# funky_super_usb_r2.net
KiCad netlist of a schematic drawn in EAGLE
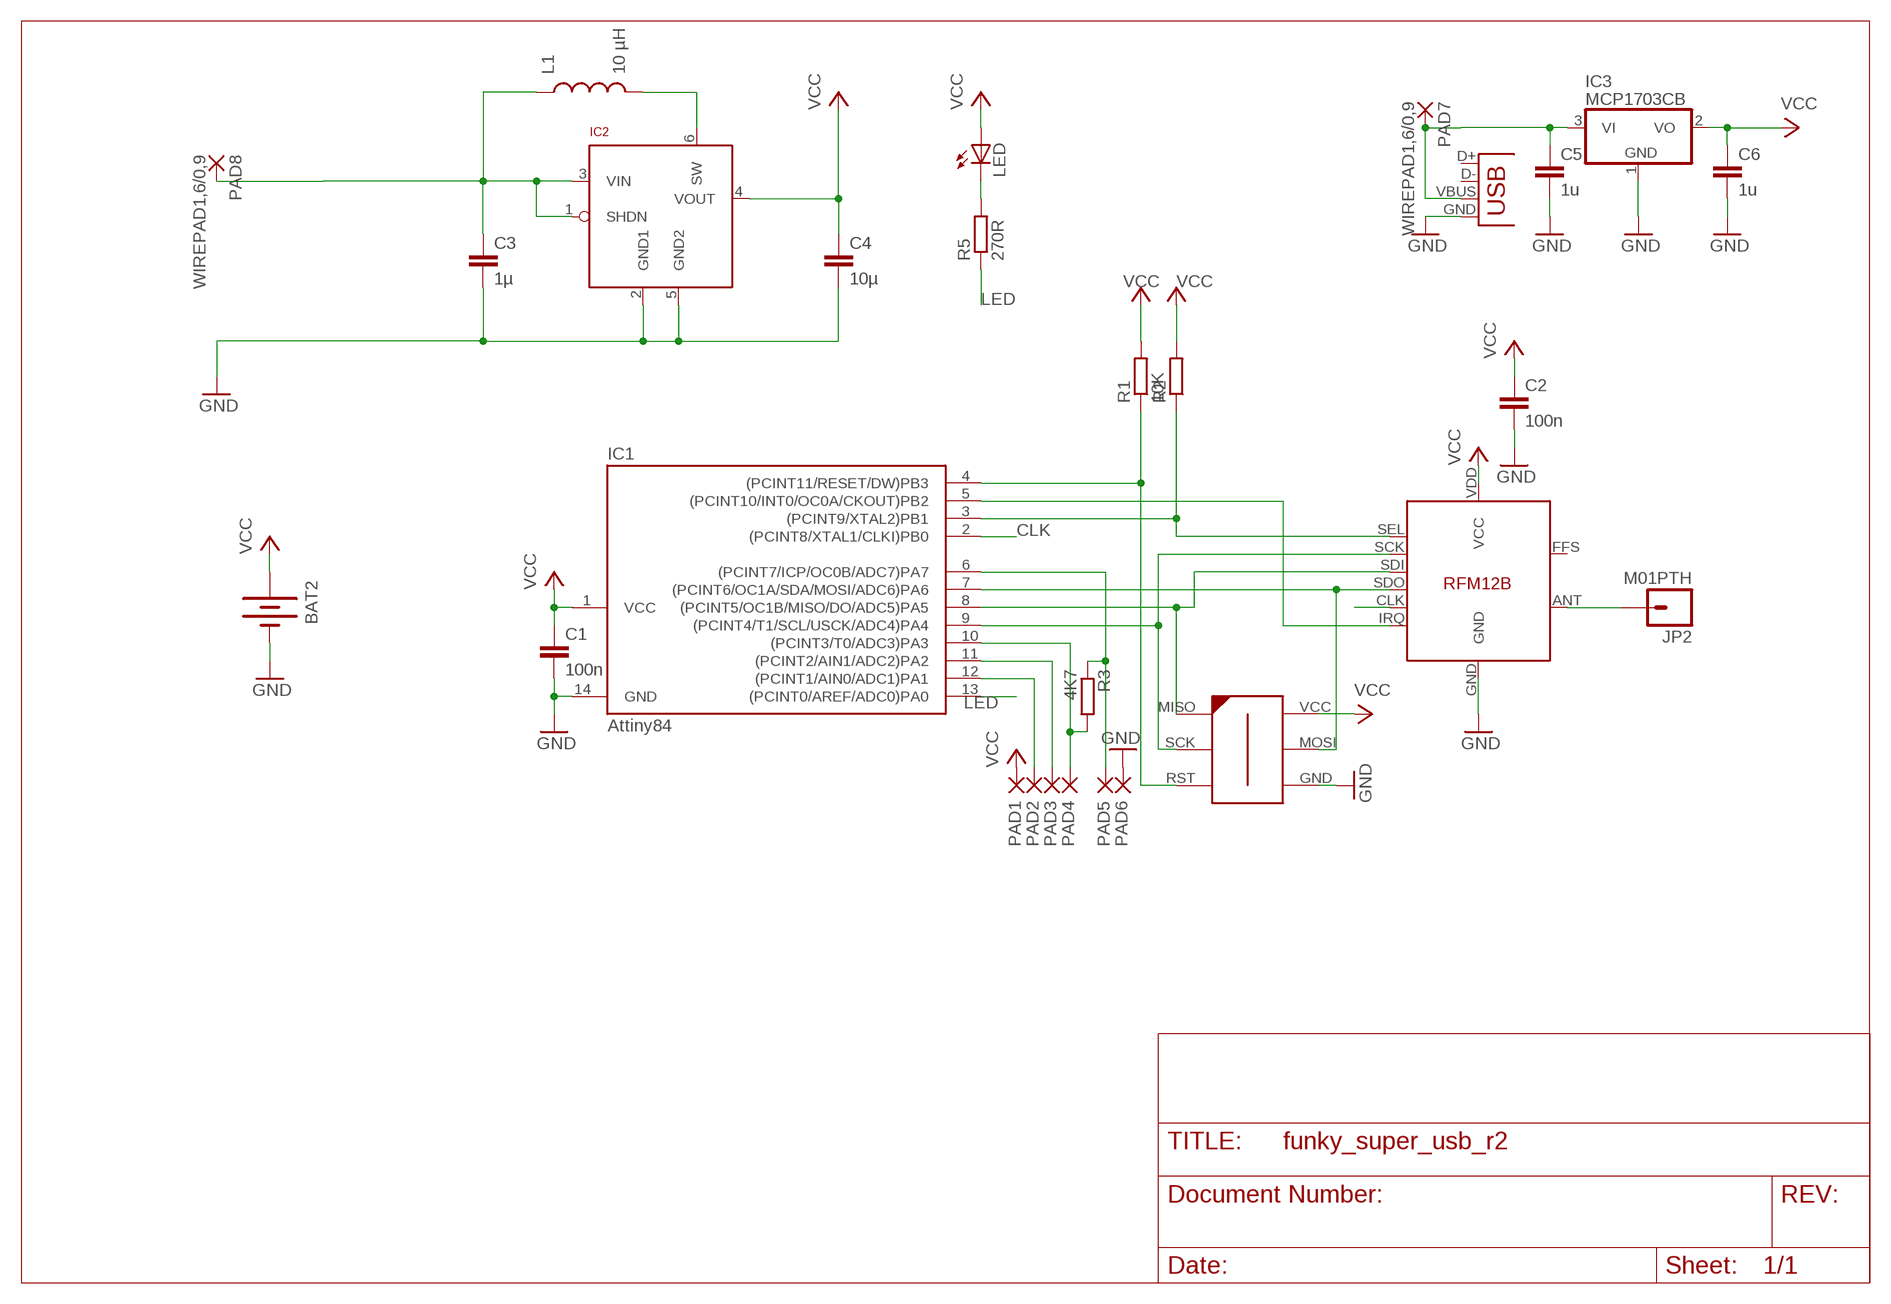
[diagram p0: schematic, sheet 1]

(export (version "E")
  (design (tool "Eeschema 10.0.6"))
  (components
    (comp (ref "BAT2")
      (value "BATTERY20PTH")
      (footprint "eagle-import:BATTCOM_20MM_PTH")
      (libsource (lib "eagle-import") (part "BATTERY20PTH"))
    )
    (comp (ref "C1")
      (value "100n")
      (footprint "eagle-import:C0603K")
      (libsource (lib "eagle-import") (part "C-EUC0603K"))
    )
    (comp (ref "C2")
      (value "100n")
      (footprint "eagle-import:C0603K")
      (libsource (lib "eagle-import") (part "C-EUC0603K"))
    )
    (comp (ref "C3")
      (value "1µ")
      (footprint "eagle-import:0603-CAP")
      (libsource (lib "eagle-import") (part "CAP0603-CAP"))
    )
    (comp (ref "C4")
      (value "10µ")
      (footprint "eagle-import:0805")
      (libsource (lib "eagle-import") (part "CAP0805"))
    )
    (comp (ref "C5")
      (value "1u")
      (footprint "eagle-import:C0603K")
      (libsource (lib "eagle-import") (part "C-EUC0603K"))
    )
    (comp (ref "C6")
      (value "1u")
      (footprint "eagle-import:C0603K")
      (libsource (lib "eagle-import") (part "C-EUC0603K"))
    )
    (comp (ref "IC1")
      (value "Attiny84")
      (footprint "eagle-import:SOIC14")
      (libsource (lib "eagle-import") (part "TINY24/44/84-SSU"))
    )
    (comp (ref "IC2")
      (value "LTC3525")
      (footprint "eagle-import:SC70")
      (libsource (lib "eagle-import") (part "LTC3525"))
    )
    (comp (ref "IC3")
      (value "MCP1703CB")
      (footprint "eagle-import:SOT23")
      (libsource (lib "eagle-import") (part "MCP1703CB"))
    )
    (comp (ref "JP2")
      (value "M01PTH")
      (footprint "eagle-import:1X01")
      (libsource (lib "eagle-import") (part "M01PTH"))
    )
    (comp (ref "L1")
      (value "10 µH")
      (footprint "eagle-import:1210")
      (libsource (lib "eagle-import") (part "INDUCTOR1210"))
    )
    (comp (ref "LED")
      (value "LED0603")
      (footprint "eagle-import:LED-0603")
      (libsource (lib "eagle-import") (part "LED0603"))
    )
    (comp (ref "PAD1")
      (value "SMD2")
      (footprint "eagle-import:SMD1,27-2,54")
      (libsource (lib "eagle-import") (part "SMD2"))
    )
    (comp (ref "PAD2")
      (value "SMD2")
      (footprint "eagle-import:SMD1,27-2,54")
      (libsource (lib "eagle-import") (part "SMD2"))
    )
    (comp (ref "PAD3")
      (value "SMD2")
      (footprint "eagle-import:SMD1,27-2,54")
      (libsource (lib "eagle-import") (part "SMD2"))
    )
    (comp (ref "PAD4")
      (value "SMD2")
      (footprint "eagle-import:SMD1,27-2,54")
      (libsource (lib "eagle-import") (part "SMD2"))
    )
    (comp (ref "PAD5")
      (value "SMD2")
      (footprint "eagle-import:SMD1,27-2,54")
      (libsource (lib "eagle-import") (part "SMD2"))
    )
    (comp (ref "PAD6")
      (value "SMD2")
      (footprint "eagle-import:SMD1,27-2,54")
      (libsource (lib "eagle-import") (part "SMD2"))
    )
    (comp (ref "PAD7")
      (value "WIREPAD1,6/0,9")
      (footprint "eagle-import:1,6_0,9")
      (libsource (lib "eagle-import") (part "WIREPAD1,6/0,9"))
    )
    (comp (ref "PAD8")
      (value "WIREPAD1,6/0,9")
      (footprint "eagle-import:1,6_0,9")
      (libsource (lib "eagle-import") (part "WIREPAD1,6/0,9"))
    )
    (comp (ref "R1")
      (value "10K")
      (footprint "eagle-import:R0603")
      (libsource (lib "eagle-import") (part "R-EU_R0603"))
    )
    (comp (ref "R2")
      (value "R-EU_R0603")
      (footprint "eagle-import:R0603")
      (libsource (lib "eagle-import") (part "R-EU_R0603"))
    )
    (comp (ref "R3")
      (value "4K7")
      (footprint "eagle-import:R0603")
      (libsource (lib "eagle-import") (part "R-EU_R0603"))
    )
    (comp (ref "R5")
      (value "270R")
      (footprint "eagle-import:R0603")
      (libsource (lib "eagle-import") (part "R-EU_R0603"))
    )
    (comp (ref "RFM12B")
      (value "RFM12B")
      (footprint "eagle-import:RFM12B")
      (libsource (lib "eagle-import") (part "RFM12B"))
    )
    (comp (ref "U$2")
      (value "AVR-ISP-6-EDGE")
      (footprint "eagle-import:6PAD_ISP")
      (libsource (lib "eagle-import") (part "AVR-ISP-6-EDGE"))
    )
    (comp (ref "X1")
      (value "USB-MICROB")
      (footprint "eagle-import:USB-MICROB")
      (libsource (lib "eagle-import") (part "USB-MICROB"))
    )
  )
  (nets
    (net (code "1") (name "/CLK") (class "Default")
      (node (ref "IC1") (pin "2") (pinfunction "(PCINT8/XTAL1/CLKI)PB0_2") (pintype "bidirectional"))
      (node (ref "RFM12B") (pin "CLK") (pinfunction "CLK_CLK") (pintype "output"))
    )
    (net (code "2") (name "/LED") (class "Default")
      (node (ref "IC1") (pin "13") (pinfunction "(PCINT0/AREF/ADC0)PA0_13") (pintype "bidirectional"))
      (node (ref "R5") (pin "1") (pinfunction "1_1") (pintype "passive"))
    )
    (net (code "3") (name "GND") (class "Default")
      (node (ref "BAT2") (pin "2") (pinfunction "-_2") (pintype "power_in"))
      (node (ref "C1") (pin "2") (pinfunction "2_2") (pintype "passive"))
      (node (ref "C2") (pin "2") (pinfunction "2_2") (pintype "passive"))
      (node (ref "C3") (pin "2") (pinfunction "2_2") (pintype "passive"))
      (node (ref "C4") (pin "2") (pinfunction "2_2") (pintype "passive"))
      (node (ref "C5") (pin "2") (pinfunction "2_2") (pintype "passive"))
      (node (ref "C6") (pin "2") (pinfunction "2_2") (pintype "passive"))
      (node (ref "IC1") (pin "14") (pinfunction "GND_14") (pintype "power_in"))
      (node (ref "IC2") (pin "2") (pinfunction "GND1_2") (pintype "power_in"))
      (node (ref "IC2") (pin "5") (pinfunction "GND2_5") (pintype "power_in"))
      (node (ref "IC3") (pin "1") (pinfunction "GND_1") (pintype "passive"))
      (node (ref "PAD6") (pin "1") (pinfunction "P_1") (pintype "passive"))
      (node (ref "RFM12B") (pin "GND") (pinfunction "GND_GND") (pintype "power_in"))
      (node (ref "U$2") (pin "GND") (pinfunction "P$4_GND") (pintype "bidirectional"))
      (node (ref "X1") (pin "GND") (pinfunction "GND_GND") (pintype "bidirectional"))
    )
    (net (code "4") (name "Net-(IC1-(PCINT1{slash}AIN0{slash}ADC1)PA1)") (class "Default")
      (node (ref "IC1") (pin "12") (pinfunction "(PCINT1/AIN0/ADC1)PA1_12") (pintype "bidirectional"))
      (node (ref "PAD2") (pin "1") (pinfunction "P_1") (pintype "passive"))
    )
    (net (code "5") (name "Net-(IC1-(PCINT2{slash}AIN1{slash}ADC2)PA2)") (class "Default")
      (node (ref "IC1") (pin "11") (pinfunction "(PCINT2/AIN1/ADC2)PA2_11") (pintype "bidirectional"))
      (node (ref "PAD3") (pin "1") (pinfunction "P_1") (pintype "passive"))
    )
    (net (code "6") (name "Net-(IC1-(PCINT3{slash}T0{slash}ADC3)PA3)") (class "Default")
      (node (ref "IC1") (pin "10") (pinfunction "(PCINT3/T0/ADC3)PA3_10") (pintype "bidirectional"))
      (node (ref "PAD4") (pin "1") (pinfunction "P_1") (pintype "passive"))
      (node (ref "R3") (pin "2") (pinfunction "2_2") (pintype "passive"))
    )
    (net (code "7") (name "Net-(IC1-(PCINT4{slash}T1{slash}SCL{slash}USCK{slash}ADC4)PA4)") (class "Default")
      (node (ref "IC1") (pin "9") (pinfunction "(PCINT4/T1/SCL/USCK/ADC4)PA4_9") (pintype "bidirectional"))
      (node (ref "RFM12B") (pin "SCK") (pinfunction "SCK_SCK") (pintype "input"))
      (node (ref "U$2") (pin "SCK") (pinfunction "P$2_SCK") (pintype "bidirectional"))
    )
    (net (code "8") (name "Net-(IC1-(PCINT5{slash}OC1B{slash}MISO{slash}DO{slash}ADC5)PA5)") (class "Default")
      (node (ref "IC1") (pin "8") (pinfunction "(PCINT5/OC1B/MISO/DO/ADC5)PA5_8") (pintype "bidirectional"))
      (node (ref "RFM12B") (pin "SDI") (pinfunction "SDI_SDI") (pintype "input"))
      (node (ref "U$2") (pin "MISO") (pinfunction "P$1_MISO") (pintype "bidirectional"))
    )
    (net (code "9") (name "Net-(IC1-(PCINT6{slash}OC1A{slash}SDA{slash}MOSI{slash}ADC6)PA6)") (class "Default")
      (node (ref "IC1") (pin "7") (pinfunction "(PCINT6/OC1A/SDA/MOSI/ADC6)PA6_7") (pintype "bidirectional"))
      (node (ref "RFM12B") (pin "SDO") (pinfunction "SDO_SDO") (pintype "output"))
      (node (ref "U$2") (pin "MOSI") (pinfunction "P$5_MOSI") (pintype "bidirectional"))
    )
    (net (code "10") (name "Net-(IC1-(PCINT7{slash}ICP{slash}OC0B{slash}ADC7)PA7)") (class "Default")
      (node (ref "IC1") (pin "6") (pinfunction "(PCINT7/ICP/OC0B/ADC7)PA7_6") (pintype "bidirectional"))
      (node (ref "PAD5") (pin "1") (pinfunction "P_1") (pintype "passive"))
      (node (ref "R3") (pin "1") (pinfunction "1_1") (pintype "passive"))
    )
    (net (code "11") (name "Net-(IC1-(PCINT9{slash}XTAL2)PB1)") (class "Default")
      (node (ref "IC1") (pin "3") (pinfunction "(PCINT9/XTAL2)PB1_3") (pintype "bidirectional"))
      (node (ref "R2") (pin "1") (pinfunction "1_1") (pintype "passive"))
      (node (ref "RFM12B") (pin "SEL") (pinfunction "SEL_SEL") (pintype "input"))
    )
    (net (code "12") (name "Net-(IC1-(PCINT10{slash}INT0{slash}OC0A{slash}CKOUT)PB2)") (class "Default")
      (node (ref "IC1") (pin "5") (pinfunction "(PCINT10/INT0/OC0A/CKOUT)PB2_5") (pintype "bidirectional"))
      (node (ref "RFM12B") (pin "IRQ") (pinfunction "IRQ_IRQ") (pintype "open_collector"))
    )
    (net (code "13") (name "Net-(IC1-(PCINT11{slash}RESET{slash}DW)PB3)") (class "Default")
      (node (ref "IC1") (pin "4") (pinfunction "(PCINT11/RESET/DW)PB3_4") (pintype "bidirectional"))
      (node (ref "R1") (pin "1") (pinfunction "1_1") (pintype "passive"))
      (node (ref "U$2") (pin "RST") (pinfunction "P$3_RST") (pintype "bidirectional"))
    )
    (net (code "14") (name "Net-(IC2-SHDN)") (class "Default")
      (node (ref "C3") (pin "1") (pinfunction "1_1") (pintype "passive"))
      (node (ref "IC2") (pin "1") (pinfunction "SHDN_1") (pintype "input"))
      (node (ref "IC2") (pin "3") (pinfunction "VIN_3") (pintype "tri_state"))
      (node (ref "L1") (pin "1") (pinfunction "1_1") (pintype "passive"))
      (node (ref "PAD8") (pin "1") (pinfunction "P_1") (pintype "passive"))
    )
    (net (code "15") (name "Net-(IC2-SW)") (class "Default")
      (node (ref "IC2") (pin "6") (pinfunction "SW_6") (pintype "power_in"))
      (node (ref "L1") (pin "2") (pinfunction "2_2") (pintype "passive"))
    )
    (net (code "16") (name "Net-(IC3-VI)") (class "Default")
      (node (ref "C5") (pin "1") (pinfunction "1_1") (pintype "passive"))
      (node (ref "IC3") (pin "3") (pinfunction "VI_3") (pintype "input"))
      (node (ref "PAD7") (pin "1") (pinfunction "P_1") (pintype "passive"))
      (node (ref "X1") (pin "VBUS") (pinfunction "VBUS_VBUS") (pintype "bidirectional"))
    )
    (net (code "17") (name "Net-(JP2-Pad1)") (class "Default")
      (node (ref "JP2") (pin "1") (pinfunction "1_1") (pintype "passive"))
      (node (ref "RFM12B") (pin "ANT") (pinfunction "ANT_ANT") (pintype "passive"))
    )
    (net (code "18") (name "Net-(LED-PadC)") (class "Default")
      (node (ref "LED") (pin "C") (pinfunction "C_C") (pintype "passive"))
      (node (ref "R5") (pin "2") (pinfunction "2_2") (pintype "passive"))
    )
    (net (code "19") (name "VCC") (class "Default")
      (node (ref "BAT2") (pin "1") (pinfunction "+_1") (pintype "power_in"))
      (node (ref "C1") (pin "1") (pinfunction "1_1") (pintype "passive"))
      (node (ref "C2") (pin "1") (pinfunction "1_1") (pintype "passive"))
      (node (ref "C4") (pin "1") (pinfunction "1_1") (pintype "passive"))
      (node (ref "C6") (pin "1") (pinfunction "1_1") (pintype "passive"))
      (node (ref "IC1") (pin "1") (pinfunction "VCC_1") (pintype "power_in"))
      (node (ref "IC2") (pin "4") (pinfunction "VOUT_4") (pintype "power_in"))
      (node (ref "IC3") (pin "2") (pinfunction "VO_2") (pintype "passive"))
      (node (ref "LED") (pin "A") (pinfunction "A_A") (pintype "passive"))
      (node (ref "PAD1") (pin "1") (pinfunction "P_1") (pintype "passive"))
      (node (ref "R1") (pin "2") (pinfunction "2_2") (pintype "passive"))
      (node (ref "R2") (pin "2") (pinfunction "2_2") (pintype "passive"))
      (node (ref "RFM12B") (pin "VDD") (pinfunction "VCC_VDD") (pintype "power_in"))
      (node (ref "U$2") (pin "VCC") (pinfunction "P$6_VCC") (pintype "bidirectional"))
    )
    (net (code "20") (name "unconnected-(RFM12B-PadFFS)") (class "Default")
      (node (ref "RFM12B") (pin "FFS") (pinfunction "FFS_FFS") (pintype "bidirectional"))
    )
    (net (code "21") (name "unconnected-(X1-PadD+)") (class "Default")
      (node (ref "X1") (pin "D+") (pinfunction "D+_D+") (pintype "bidirectional"))
    )
    (net (code "22") (name "unconnected-(X1-PadD-)") (class "Default")
      (node (ref "X1") (pin "D-") (pinfunction "D-_D-") (pintype "bidirectional"))
    )
  )
)
